# Power_Supplies.net
KiCad netlist of a schematic drawn in Altium Designer
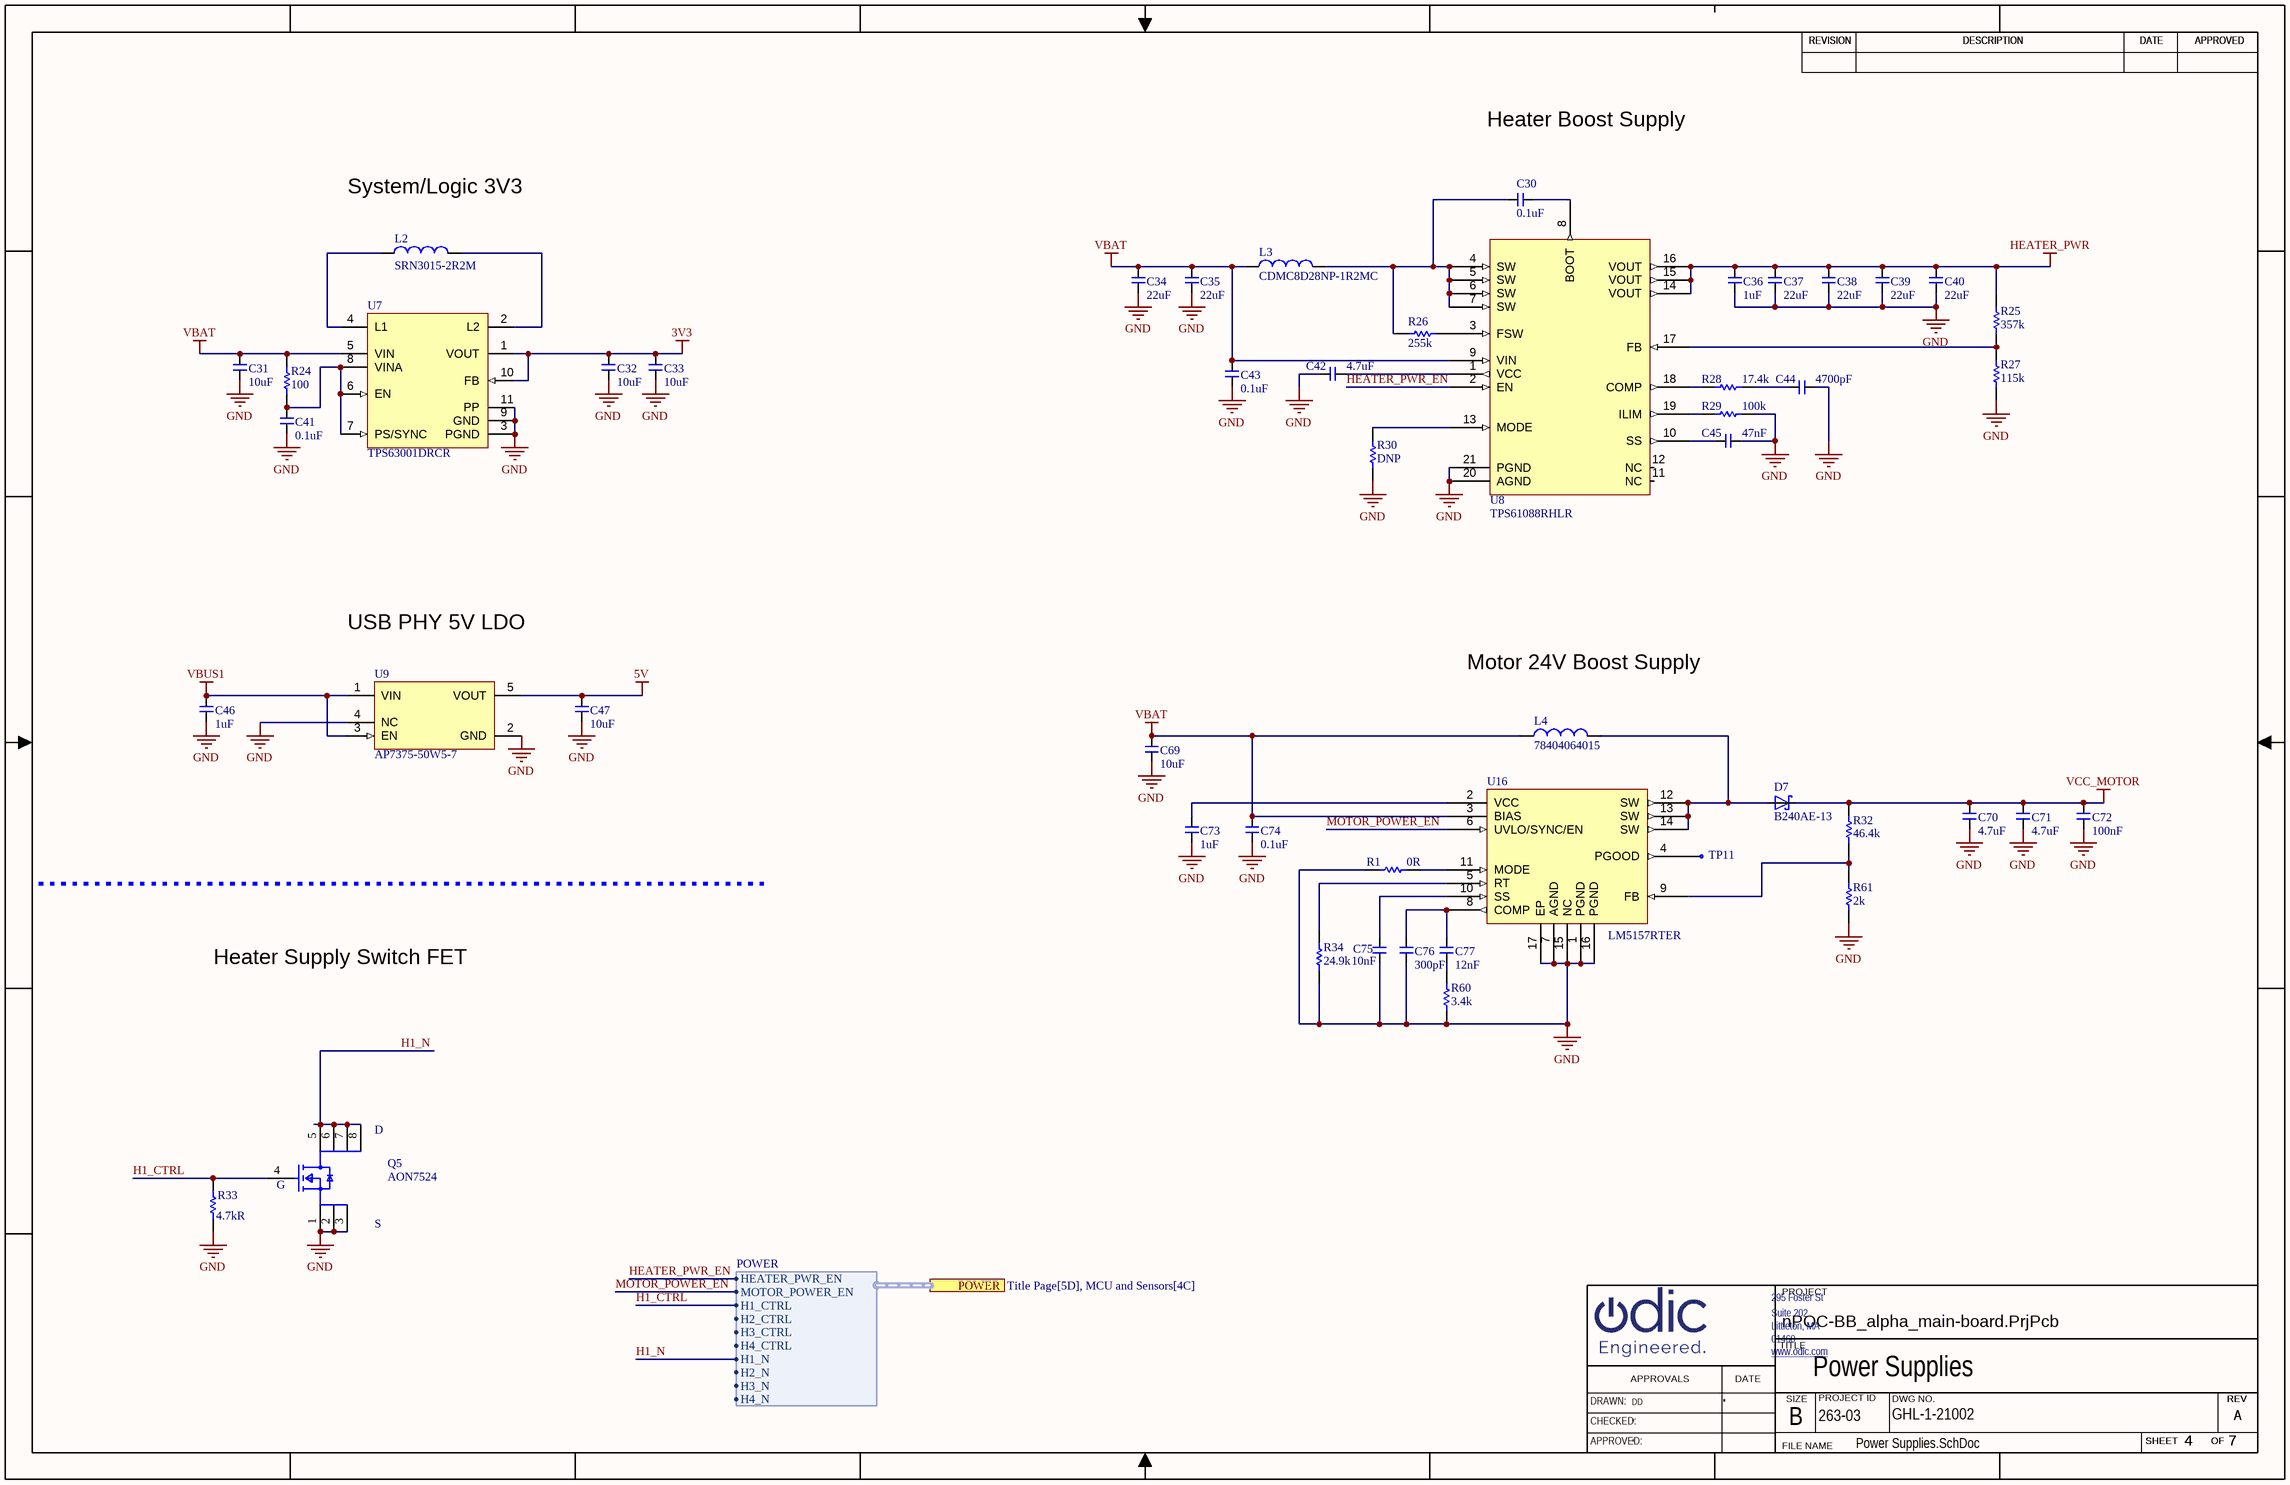
[diagram p0: Power Supplies.SchDoc]

(export (version "E")
  (design (tool "Eeschema 10.0.6"))
  (components
    (comp (ref "C30")
      (value "0.1uF")
      (footprint "C0402")
      (description "Ceramic capacitor SMD 0402 100nF 16V X7R 10%")
      (fields (field (name "VOLTAGE") "16V") (field (name "TOLERANCE") "10%"))
      (libsource (lib "Odic Inc") (part "cAP"))
    )
    (comp (ref "C31")
      (value "10uF")
      (footprint "C0603")
      (description "Cap Ceramic 10uF 35V X5R 20% Pad SMD 0603 85C T/R")
      (fields (field (name "TOLERANCE") "20%"))
      (libsource (lib "Odic Inc") (part "cAP"))
    )
    (comp (ref "C32")
      (value "10uF")
      (footprint "C0402")
      (description "Cap Ceramic 10uF 6.3V X5R 20% SMD 0402 85°C Paper T/R")
      (fields (field (name "TOLERANCE") "20%"))
      (libsource (lib "Odic Inc") (part "cAP"))
    )
    (comp (ref "C33")
      (value "10uF")
      (footprint "C0402")
      (description "Cap Ceramic 10uF 6.3V X5R 20% SMD 0402 85°C Paper T/R")
      (fields (field (name "TOLERANCE") "20%"))
      (libsource (lib "Odic Inc") (part "cAP"))
    )
    (comp (ref "C34")
      (value "22uF")
      (footprint "c0805")
      (description "Multilayer Ceramic Capacitor, 22 uF, 25 V, ± 20%, X5R, 0805 [2012 Metric]")
      (libsource (lib "Odic Inc") (part "cAP"))
    )
    (comp (ref "C35")
      (value "22uF")
      (footprint "c0805")
      (description "Multilayer Ceramic Capacitor, 22 uF, 25 V, ± 20%, X5R, 0805 [2012 Metric]")
      (libsource (lib "Odic Inc") (part "cAP"))
    )
    (comp (ref "C36")
      (value "1uF")
      (footprint "C0603")
      (description "Multilayer Ceramic Capacitors MLCC - SMD/SMT 1uF 50V 0603 RoHS")
      (fields (field (name "TOLERANCE") "10%"))
      (libsource (lib "Odic Inc") (part "cAP"))
    )
    (comp (ref "C37")
      (value "22uF")
      (footprint "c0805")
      (description "Multilayer Ceramic Capacitor, 22 uF, 25 V, ± 20%, X5R, 0805 [2012 Metric]")
      (libsource (lib "Odic Inc") (part "cAP"))
    )
    (comp (ref "C38")
      (value "22uF")
      (footprint "c0805")
      (description "Multilayer Ceramic Capacitor, 22 uF, 25 V, ± 20%, X5R, 0805 [2012 Metric]")
      (libsource (lib "Odic Inc") (part "cAP"))
    )
    (comp (ref "C39")
      (value "22uF")
      (footprint "c0805")
      (description "Multilayer Ceramic Capacitor, 22 uF, 25 V, ± 20%, X5R, 0805 [2012 Metric]")
      (libsource (lib "Odic Inc") (part "cAP"))
    )
    (comp (ref "C40")
      (value "22uF")
      (footprint "c0805")
      (description "Multilayer Ceramic Capacitor, 22 uF, 25 V, ± 20%, X5R, 0805 [2012 Metric]")
      (libsource (lib "Odic Inc") (part "cAP"))
    )
    (comp (ref "C41")
      (value "0.1uF")
      (footprint "C0402")
      (description "Cap Ceramic 0.1uF 25V X5R 10% Pad SMD 0402 Multi Layer Ceramic Capacitor (MLCC)")
      (fields (field (name "VOLTAGE") "25V") (field (name "TOLERANCE") "10%"))
      (libsource (lib "Odic Inc") (part "cAP"))
    )
    (comp (ref "C42")
      (value "4.7uF")
      (footprint "C0402")
      (description "Cap Ceramic 4.7uF 10V X5R 20% SMD 0402 85°C Paper T/R")
      (fields (field (name "TOLERANCE") "20%"))
      (libsource (lib "Odic Inc") (part "cAP"))
    )
    (comp (ref "C43")
      (value "0.1uF")
      (footprint "C0402")
      (description "Ceramic capacitor SMD 0402 100nF 16V X7R 10%")
      (fields (field (name "VOLTAGE") "16V") (field (name "TOLERANCE") "10%"))
      (libsource (lib "Odic Inc") (part "cAP"))
    )
    (comp (ref "C44")
      (value "4700pF")
      (footprint "C0402")
      (description "0402 4.7 nF 25 V ±10 % Tolerance X7R SMT Multilayer Ceramic Capacitor")
      (fields (field (name "TOLERANCE") "10%"))
      (libsource (lib "Odic Inc") (part "cAP"))
    )
    (comp (ref "C45")
      (value "47nF")
      (footprint "C0402")
      (description "CGA2B3X7R1H473K050BB")
      (fields (field (name "TOLERANCE") "10%"))
      (libsource (lib "Odic Inc") (part "cAP"))
    )
    (comp (ref "C46")
      (value "1uF")
      (footprint "C0603")
      (description "Multilayer Ceramic Capacitors MLCC - SMD/SMT 1uF 50V 0603 RoHS")
      (fields (field (name "TOLERANCE") "10%"))
      (libsource (lib "Odic Inc") (part "cAP"))
    )
    (comp (ref "C47")
      (value "10uF")
      (footprint "C0402")
      (description "Ceramic capacitor SMD; 0402; 10uF; 10V; X5R; 20%")
      (fields (field (name "TOLERANCE") "20%"))
      (libsource (lib "Odic Inc") (part "cAP"))
    )
    (comp (ref "C69")
      (value "10uF")
      (footprint "C0603")
      (description "Cap Ceramic 10uF 35V X5R 20% Pad SMD 0603 85C T/R")
      (fields (field (name "TOLERANCE") "20%"))
      (libsource (lib "Odic Inc") (part "cAP"))
    )
    (comp (ref "C70")
      (value "4.7uF")
      (footprint "c0805")
      (description "Multilayer Ceramic Capacitor, 4.7 uF, 35 V, ± 10%, X7S, 0805 [2012 Metric]")
      (fields (field (name "TOLERANCE") "10%"))
      (libsource (lib "Odic Inc") (part "cAP"))
    )
    (comp (ref "C71")
      (value "4.7uF")
      (footprint "c0805")
      (description "Multilayer Ceramic Capacitor, 4.7 uF, 35 V, ± 10%, X7S, 0805 [2012 Metric]")
      (fields (field (name "TOLERANCE") "10%"))
      (libsource (lib "Odic Inc") (part "cAP"))
    )
    (comp (ref "C72")
      (value "100nF")
      (footprint "C0603")
      (description "CAP CER 0.1UF 50V X7R 0603")
      (fields (field (name "TOLERANCE") "10%"))
      (libsource (lib "Odic Inc") (part "cAP"))
    )
    (comp (ref "C73")
      (value "1uF")
      (footprint "C0603")
      (description "CAP CER 1UF 16V X5R 0603")
      (fields (field (name "TOLERANCE") "10%") (field (name "VOLTAGE") "16V"))
      (libsource (lib "Odic Inc") (part "cAP"))
    )
    (comp (ref "C74")
      (value "0.1uF")
      (footprint "c0805")
      (description "Cap Cer 0.1UF 25V X7R 0805")
      (fields (field (name "TOLERANCE") "10%"))
      (libsource (lib "Odic Inc") (part "cAP"))
    )
    (comp (ref "C75")
      (value "10nF")
      (footprint "C0402")
      (description "Multilayer Ceramic Capacitor, 0.01 uF, 35 V, ± 10%, X7R, 0402 [1005 Metric]")
      (fields (field (name "TOLERANCE") "10%") (field (name "Comment") "C0402_10n_35V_10pct"))
      (libsource (lib "Odic Inc") (part "cAP"))
    )
    (comp (ref "C76")
      (value "300pF")
      (footprint "C0402")
      (description "Cap Ceramic 300pF 50V C0G 5% SMD 0402 125°C Paper T/R")
      (fields (field (name "TOLERANCE") "5%"))
      (libsource (lib "Odic Inc") (part "cAP"))
    )
    (comp (ref "C77")
      (value "12nF")
      (footprint "C0402")
      (description "0402 12 nF 16 V ±10% Tolerance X7R SMT Multilayer Ceramic Capacitor")
      (fields (field (name "VOLTAGE") "16V") (field (name "TOLERANCE") "10%"))
      (libsource (lib "Odic Inc") (part "cAP"))
    )
    (comp (ref "D7")
      (value "B240AE-13")
      (footprint "sma")
      (description "Diode Schottky 40V 2A 2-Pin DO-214AC T/R")
      (libsource (lib "Odic Inc") (part "B240AE-13"))
    )
    (comp (ref "L2")
      (value "SRN3015-2R2M")
      (footprint "IND_BOURNS_SRN3015")
      (description "Ind Power Semi-Shielded Wirewound 2.2uH 20% 1MHz Ferrite 1.8A 1212 T/R")
      (fields (field (name "TOLERANCE") "20%"))
      (libsource (lib "Odic Inc") (part "SRN3015-2R2M"))
    )
    (comp (ref "L3")
      (value "CDMC8D28NP-1R2MC")
      (footprint "ind2_9p5x8p5mm")
      (description "Inductor Power Shielded Wirewound 1.2uH 20% 1MHz 12.9A 0.007Ohm DCR T/R")
      (fields (field (name "TOLERANCE") "20%"))
      (libsource (lib "Odic Inc") (part "IND"))
    )
    (comp (ref "L4")
      (value "78404064015")
      (footprint "ind2_wurth_78404064015")
      (description "WE-LQSA SMT Semi-Shielded Power Inductor 1.5uH 6.1 A 13mOhm Max")
      (libsource (lib "Odic Inc") (part "IND"))
    )
    (comp (ref "Q5")
      (value "AON7524")
      (footprint "dfn8_3x3_p65mm_fet")
      (description "Trans Mosfet N-ch 30V 28A 8-PIN Dfn-a Ep")
      (libsource (lib "Odic Inc") (part "e0baf4780622716b99a4fe4ad34e686"))
    )
    (comp (ref "R1")
      (value "0R")
      (footprint "R0402")
      (description "RES 0 OHM JUMPER 1/16W 0402")
      (libsource (lib "Odic Inc") (part "RES"))
    )
    (comp (ref "R24")
      (value "100")
      (footprint "R0402")
      (description "Res General Purpose Thick Film 0402 100 Ohm 1% 1/16W ±200ppm/°C Molded SMD Paper T/R")
      (fields (field (name "TOLERANCE") "1%"))
      (libsource (lib "Odic Inc") (part "RES"))
    )
    (comp (ref "R25")
      (value "357k")
      (footprint "R0402")
      (description "Res Thick Film 0402 357K Ohm 1% 0.1W ±100ppm/°C Molded SMD Punched Carrier T/R")
      (fields (field (name "TOLERANCE") "1%"))
      (libsource (lib "Odic Inc") (part "RES"))
    )
    (comp (ref "R26")
      (value "255k")
      (footprint "R0402")
      (description "SMD Chip Resistor, 255 kOhm, ± 1%, 100 mW, 0402 [1005 Metric], Thick Film, Precision")
      (fields (field (name "TOLERANCE") "1%"))
      (libsource (lib "Odic Inc") (part "RES"))
    )
    (comp (ref "R27")
      (value "115k")
      (footprint "R0402")
      (description "SMD Chip Resistor, 115 kOhm, ± 1%, 100 mW, 0402 [1005 Metric], Thick Film, Precision")
      (fields (field (name "TOLERANCE") "1%"))
      (libsource (lib "Odic Inc") (part "RES"))
    )
    (comp (ref "R28")
      (value "17.4k")
      (footprint "R0402")
      (description "Res Thick Film 0402 17.4K Ohm 1% 1/10W ±100ppm/°C Molded SMD Punched Carrier T/R")
      (fields (field (name "TOLERANCE") "1%"))
      (libsource (lib "Odic Inc") (part "RES"))
    )
    (comp (ref "R29")
      (value "100k")
      (footprint "R0402")
      (description "Res General Purpose Thick Film 0402 100K Ohm 1% 1/16W ±100ppm/°C Molded SMD Paper T/R")
      (fields (field (name "TOLERANCE") "1%"))
      (libsource (lib "Odic Inc") (part "RES"))
    )
    (comp (ref "R30")
      (value "DNP")
      (footprint "R0402")
      (description "Unpopulated 0402 pads. No part number associated with this \"component\"")
      (libsource (lib "Odic Inc") (part "RES"))
    )
    (comp (ref "R32")
      (value "46.4k")
      (footprint "R0402")
      (description "Resistor, Metal Glaze/Thick Film, 0.1 W, 1 %, 100 Ppm, 46400 Ohm, Surface Mount, 0402")
      (fields (field (name "TOLERANCE") "1%"))
      (libsource (lib "Odic Inc") (part "RES"))
    )
    (comp (ref "R33")
      (value "R0402_4k7_1pct")
      (footprint "R0402")
      (description "RES 4.7K OHM 1% 1/16W 0402")
      (fields (field (name "TOLERANCE") "1%") (field (name "RESISTANCE") "4.7kR"))
      (libsource (lib "Odic Inc") (part "RES"))
    )
    (comp (ref "R34")
      (value "24.9k")
      (footprint "R0402")
      (description "Res Thick Film 0402 24.9K Ohm 1% 1/10W ±100ppm/¦C SMD Punched Carrier T/R")
      (fields (field (name "TOLERANCE") "1%"))
      (libsource (lib "Odic Inc") (part "RES"))
    )
    (comp (ref "R60")
      (value "3.4k")
      (footprint "R0402")
      (description "SMD Chip Resistor, 3.4 kOhm, ± 1%, 100 mW, 0402 [1005 Metric], Thick Film, Precision")
      (fields (field (name "TOLERANCE") "1%"))
      (libsource (lib "Odic Inc") (part "RES"))
    )
    (comp (ref "R61")
      (value "2k")
      (footprint "R0402")
      (description "Res General Purpose Thick Film 0402 2K Ohm 1% 1/16W ±100ppm/°C Molded SMD Paper T/R")
      (fields (field (name "TOLERANCE") "1%"))
      (libsource (lib "Odic Inc") (part "RES"))
    )
    (comp (ref "TP11")
      (value "TPC30")
      (footprint "tpc30")
      (description "Test Point Circle 30")
      (libsource (lib "Odic Inc") (part "TPC"))
    )
    (comp (ref "U7")
      (value "TPS63001DRCR")
      (footprint "dfn10_3x3_p5mm_1mm")
      (description "IC REG BUCK BST 3.3V 1.6A 10SON, FIXED 3.3V")
      (libsource (lib "Odic Inc") (part "TPS6300x"))
    )
    (comp (ref "U8")
      (value "TPS61088RHLR")
      (footprint "qfn20_3p5x4p5_p5mm")
      (description "IC REG BOOST ADJ 10A SYNC 20VQFN")
      (libsource (lib "Odic Inc") (part "TPS61088RHLR-Symbol-1"))
    )
    (comp (ref "U9")
      (value "AP7375-50W5-7")
      (footprint "SOT25")
      (description "Fixed 5V LDO Voltage Regulators LDO CMOS LowCurr SOT23 TR 3K")
      (libsource (lib "Odic Inc") (part "0611416dd6b6fc2280b1ddb1fddec67"))
    )
    (comp (ref "U16")
      (value "LM5157RTER")
      (footprint "qfn16_3x3_p5mm_thpad")
      (libsource (lib "Odic Inc") (part "LM5157RTER-Symbol-1"))
    )
  )
  (nets
    (net (code "2") (name "/H1_CTRL") (class "Default")
      (node (ref "Q5") (pin "4") (pinfunction "G_4") (pintype "passive"))
      (node (ref "R33") (pin "2") (pinfunction "2_2") (pintype "passive"))
    )
    (net (code "3") (name "/H1_N") (class "Default")
      (node (ref "Q5") (pin "5") (pinfunction "D_5") (pintype "passive"))
      (node (ref "Q5") (pin "6") (pinfunction "D_6") (pintype "passive"))
      (node (ref "Q5") (pin "7") (pinfunction "D_7") (pintype "passive"))
      (node (ref "Q5") (pin "8") (pinfunction "D_8") (pintype "passive"))
    )
    (net (code "4") (name "/HEATER_PWR_EN") (class "Default")
      (node (ref "U8") (pin "2") (pinfunction "EN_2") (pintype "input"))
    )
    (net (code "5") (name "/MOTOR_POWER_EN") (class "Default")
      (node (ref "U16") (pin "6") (pinfunction "UVLO/SYNC/EN_6") (pintype "input"))
    )
    (net (code "7") (name "3V3") (class "Default")
      (node (ref "C32") (pin "2") (pinfunction "2_2") (pintype "passive"))
      (node (ref "C33") (pin "2") (pinfunction "2_2") (pintype "passive"))
      (node (ref "U7") (pin "1") (pinfunction "VOUT_1") (pintype "power_in"))
      (node (ref "U7") (pin "10") (pinfunction "FB_10") (pintype "input"))
    )
    (net (code "8") (name "5V") (class "Default")
      (node (ref "C47") (pin "2") (pinfunction "2_2") (pintype "passive"))
      (node (ref "U9") (pin "5") (pinfunction "VOUT_5") (pintype "power_in"))
    )
    (net (code "9") (name "GND") (class "Default")
      (node (ref "C31") (pin "1") (pinfunction "1_1") (pintype "passive"))
      (node (ref "C32") (pin "1") (pinfunction "1_1") (pintype "passive"))
      (node (ref "C33") (pin "1") (pinfunction "1_1") (pintype "passive"))
      (node (ref "C34") (pin "1") (pinfunction "1_1") (pintype "passive"))
      (node (ref "C35") (pin "1") (pinfunction "1_1") (pintype "passive"))
      (node (ref "C36") (pin "1") (pinfunction "1_1") (pintype "passive"))
      (node (ref "C37") (pin "1") (pinfunction "1_1") (pintype "passive"))
      (node (ref "C38") (pin "1") (pinfunction "1_1") (pintype "passive"))
      (node (ref "C39") (pin "1") (pinfunction "1_1") (pintype "passive"))
      (node (ref "C40") (pin "1") (pinfunction "1_1") (pintype "passive"))
      (node (ref "C41") (pin "1") (pinfunction "1_1") (pintype "passive"))
      (node (ref "C42") (pin "1") (pinfunction "1_1") (pintype "passive"))
      (node (ref "C43") (pin "1") (pinfunction "1_1") (pintype "passive"))
      (node (ref "C44") (pin "2") (pinfunction "2_2") (pintype "passive"))
      (node (ref "C45") (pin "2") (pinfunction "2_2") (pintype "passive"))
      (node (ref "C46") (pin "1") (pinfunction "1_1") (pintype "passive"))
      (node (ref "C47") (pin "1") (pinfunction "1_1") (pintype "passive"))
      (node (ref "C69") (pin "1") (pinfunction "1_1") (pintype "passive"))
      (node (ref "C70") (pin "1") (pinfunction "1_1") (pintype "passive"))
      (node (ref "C71") (pin "1") (pinfunction "1_1") (pintype "passive"))
      (node (ref "C72") (pin "1") (pinfunction "1_1") (pintype "passive"))
      (node (ref "C73") (pin "1") (pinfunction "1_1") (pintype "passive"))
      (node (ref "C74") (pin "1") (pinfunction "1_1") (pintype "passive"))
      (node (ref "C75") (pin "1") (pinfunction "1_1") (pintype "passive"))
      (node (ref "C76") (pin "1") (pinfunction "1_1") (pintype "passive"))
      (node (ref "Q5") (pin "1") (pinfunction "S_1") (pintype "passive"))
      (node (ref "Q5") (pin "2") (pinfunction "S_2") (pintype "passive"))
      (node (ref "Q5") (pin "3") (pinfunction "S_3") (pintype "passive"))
      (node (ref "R1") (pin "1") (pinfunction "1_1") (pintype "passive"))
      (node (ref "R27") (pin "1") (pinfunction "1_1") (pintype "passive"))
      (node (ref "R29") (pin "2") (pinfunction "2_2") (pintype "passive"))
      (node (ref "R30") (pin "1") (pinfunction "1_1") (pintype "passive"))
      (node (ref "R33") (pin "1") (pinfunction "1_1") (pintype "passive"))
      (node (ref "R34") (pin "1") (pinfunction "1_1") (pintype "passive"))
      (node (ref "R60") (pin "1") (pinfunction "1_1") (pintype "passive"))
      (node (ref "R61") (pin "1") (pinfunction "1_1") (pintype "passive"))
      (node (ref "U16") (pin "1") (pinfunction "PGND_1") (pintype "passive"))
      (node (ref "U16") (pin "15") (pinfunction "NC_15") (pintype "passive"))
      (node (ref "U16") (pin "16") (pinfunction "PGND_16") (pintype "passive"))
      (node (ref "U16") (pin "17") (pinfunction "EP_17") (pintype "passive"))
      (node (ref "U16") (pin "7") (pinfunction "AGND_7") (pintype "passive"))
      (node (ref "U7") (pin "11") (pinfunction "PP_11") (pintype "power_in"))
      (node (ref "U7") (pin "3") (pinfunction "PGND_3") (pintype "power_in"))
      (node (ref "U7") (pin "9") (pinfunction "GND_9") (pintype "power_in"))
      (node (ref "U8") (pin "20") (pinfunction "AGND_20") (pintype "passive"))
      (node (ref "U8") (pin "21") (pinfunction "PGND_21") (pintype "passive"))
      (node (ref "U9") (pin "2") (pinfunction "GND_2") (pintype "power_in"))
      (node (ref "U9") (pin "4") (pinfunction "NC_4") (pintype "passive"))
    )
    (net (code "10") (name "HEATER_PWR") (class "Default")
      (node (ref "C36") (pin "2") (pinfunction "2_2") (pintype "passive"))
      (node (ref "C37") (pin "2") (pinfunction "2_2") (pintype "passive"))
      (node (ref "C38") (pin "2") (pinfunction "2_2") (pintype "passive"))
      (node (ref "C39") (pin "2") (pinfunction "2_2") (pintype "passive"))
      (node (ref "C40") (pin "2") (pinfunction "2_2") (pintype "passive"))
      (node (ref "R25") (pin "2") (pinfunction "2_2") (pintype "passive"))
      (node (ref "U8") (pin "14") (pinfunction "VOUT_14") (pintype "output"))
      (node (ref "U8") (pin "15") (pinfunction "VOUT_15") (pintype "output"))
      (node (ref "U8") (pin "16") (pinfunction "VOUT_16") (pintype "output"))
    )
    (net (code "11") (name "Net-(C30-Pad2)") (class "Default")
      (node (ref "C30") (pin "2") (pinfunction "2_2") (pintype "passive"))
      (node (ref "L3") (pin "2") (pinfunction "2_2") (pintype "passive"))
      (node (ref "R26") (pin "1") (pinfunction "1_1") (pintype "passive"))
      (node (ref "U8") (pin "4") (pinfunction "SW_4") (pintype "input"))
      (node (ref "U8") (pin "5") (pinfunction "SW_5") (pintype "input"))
      (node (ref "U8") (pin "6") (pinfunction "SW_6") (pintype "input"))
      (node (ref "U8") (pin "7") (pinfunction "SW_7") (pintype "input"))
    )
    (net (code "12") (name "Net-(C44-Pad1)") (class "Default")
      (node (ref "C44") (pin "1") (pinfunction "1_1") (pintype "passive"))
      (node (ref "R28") (pin "2") (pinfunction "2_2") (pintype "passive"))
    )
    (net (code "13") (name "Net-(C77-Pad1)") (class "Default")
      (node (ref "C77") (pin "1") (pinfunction "1_1") (pintype "passive"))
      (node (ref "R60") (pin "2") (pinfunction "2_2") (pintype "passive"))
    )
    (net (code "14") (name "Net-(D7-PadA)") (class "Default")
      (node (ref "D7") (pin "A") (pinfunction "A_A") (pintype "passive"))
      (node (ref "L4") (pin "2") (pinfunction "2_2") (pintype "passive"))
      (node (ref "U16") (pin "12") (pinfunction "SW_12") (pintype "output"))
      (node (ref "U16") (pin "13") (pinfunction "SW_13") (pintype "output"))
      (node (ref "U16") (pin "14") (pinfunction "SW_14") (pintype "output"))
    )
    (net (code "15") (name "Net-(U7-EN)") (class "Default")
      (node (ref "C41") (pin "2") (pinfunction "2_2") (pintype "passive"))
      (node (ref "R24") (pin "1") (pinfunction "1_1") (pintype "passive"))
      (node (ref "U7") (pin "6") (pinfunction "EN_6") (pintype "input"))
      (node (ref "U7") (pin "7") (pinfunction "PS/SYNC_7") (pintype "input"))
      (node (ref "U7") (pin "8") (pinfunction "VINA_8") (pintype "power_in"))
    )
    (net (code "16") (name "Net-(U7-L1)") (class "Default")
      (node (ref "L2") (pin "1") (pinfunction "1_1") (pintype "passive"))
      (node (ref "U7") (pin "4") (pinfunction "L1_4") (pintype "passive"))
    )
    (net (code "17") (name "Net-(U7-L2)") (class "Default")
      (node (ref "L2") (pin "2") (pinfunction "2_2") (pintype "passive"))
      (node (ref "U7") (pin "2") (pinfunction "L2_2") (pintype "passive"))
    )
    (net (code "18") (name "Net-(U8-BOOT)") (class "Default")
      (node (ref "C30") (pin "1") (pinfunction "1_1") (pintype "passive"))
      (node (ref "U8") (pin "8") (pinfunction "BOOT_8") (pintype "output"))
    )
    (net (code "19") (name "Net-(U8-COMP)") (class "Default")
      (node (ref "R28") (pin "1") (pinfunction "1_1") (pintype "passive"))
      (node (ref "U8") (pin "18") (pinfunction "COMP_18") (pintype "output"))
    )
    (net (code "20") (name "Net-(U8-FB)") (class "Default")
      (node (ref "R25") (pin "1") (pinfunction "1_1") (pintype "passive"))
      (node (ref "R27") (pin "2") (pinfunction "2_2") (pintype "passive"))
      (node (ref "U8") (pin "17") (pinfunction "FB_17") (pintype "input"))
    )
    (net (code "21") (name "Net-(U8-FSW)") (class "Default")
      (node (ref "R26") (pin "2") (pinfunction "2_2") (pintype "passive"))
      (node (ref "U8") (pin "3") (pinfunction "FSW_3") (pintype "input"))
    )
    (net (code "22") (name "Net-(U8-ILIM)") (class "Default")
      (node (ref "R29") (pin "1") (pinfunction "1_1") (pintype "passive"))
      (node (ref "U8") (pin "19") (pinfunction "ILIM_19") (pintype "output"))
    )
    (net (code "23") (name "Net-(U8-MODE)") (class "Default")
      (node (ref "R30") (pin "2") (pinfunction "2_2") (pintype "passive"))
      (node (ref "U8") (pin "13") (pinfunction "MODE_13") (pintype "input"))
    )
    (net (code "24") (name "Net-(U8-SS)") (class "Default")
      (node (ref "C45") (pin "1") (pinfunction "1_1") (pintype "passive"))
      (node (ref "U8") (pin "10") (pinfunction "SS_10") (pintype "output"))
    )
    (net (code "25") (name "Net-(U8-VCC)") (class "Default")
      (node (ref "C42") (pin "2") (pinfunction "2_2") (pintype "passive"))
      (node (ref "U8") (pin "1") (pinfunction "VCC_1") (pintype "output"))
    )
    (net (code "26") (name "Net-(U16-COMP)") (class "Default")
      (node (ref "C76") (pin "2") (pinfunction "2_2") (pintype "passive"))
      (node (ref "C77") (pin "2") (pinfunction "2_2") (pintype "passive"))
      (node (ref "U16") (pin "8") (pinfunction "COMP_8") (pintype "output"))
    )
    (net (code "27") (name "Net-(U16-FB)") (class "Default")
      (node (ref "R32") (pin "1") (pinfunction "1_1") (pintype "passive"))
      (node (ref "R61") (pin "2") (pinfunction "2_2") (pintype "passive"))
      (node (ref "U16") (pin "9") (pinfunction "FB_9") (pintype "input"))
    )
    (net (code "28") (name "Net-(U16-MODE)") (class "Default")
      (node (ref "R1") (pin "2") (pinfunction "2_2") (pintype "passive"))
      (node (ref "U16") (pin "11") (pinfunction "MODE_11") (pintype "input"))
    )
    (net (code "29") (name "Net-(U16-PGOOD)") (class "Default")
      (node (ref "TP11") (pin "1") (pinfunction "1_1") (pintype "passive"))
      (node (ref "U16") (pin "4") (pinfunction "PGOOD_4") (pintype "output"))
    )
    (net (code "30") (name "Net-(U16-RT)") (class "Default")
      (node (ref "R34") (pin "2") (pinfunction "2_2") (pintype "passive"))
      (node (ref "U16") (pin "5") (pinfunction "RT_5") (pintype "input"))
    )
    (net (code "31") (name "Net-(U16-SS)") (class "Default")
      (node (ref "C75") (pin "2") (pinfunction "2_2") (pintype "passive"))
      (node (ref "U16") (pin "10") (pinfunction "SS_10") (pintype "input"))
    )
    (net (code "32") (name "Net-(U16-VCC)") (class "Default")
      (node (ref "C73") (pin "2") (pinfunction "2_2") (pintype "passive"))
      (node (ref "U16") (pin "2") (pinfunction "VCC_2") (pintype "power_in"))
    )
    (net (code "33") (name "VBAT") (class "Default")
      (node (ref "C31") (pin "2") (pinfunction "2_2") (pintype "passive"))
      (node (ref "C34") (pin "2") (pinfunction "2_2") (pintype "passive"))
      (node (ref "C35") (pin "2") (pinfunction "2_2") (pintype "passive"))
      (node (ref "C43") (pin "2") (pinfunction "2_2") (pintype "passive"))
      (node (ref "C69") (pin "2") (pinfunction "2_2") (pintype "passive"))
      (node (ref "C74") (pin "2") (pinfunction "2_2") (pintype "passive"))
      (node (ref "L3") (pin "1") (pinfunction "1_1") (pintype "passive"))
      (node (ref "L4") (pin "1") (pinfunction "1_1") (pintype "passive"))
      (node (ref "R24") (pin "2") (pinfunction "2_2") (pintype "passive"))
      (node (ref "U16") (pin "3") (pinfunction "BIAS_3") (pintype "power_in"))
      (node (ref "U7") (pin "5") (pinfunction "VIN_5") (pintype "power_in"))
      (node (ref "U8") (pin "9") (pinfunction "VIN_9") (pintype "input"))
    )
    (net (code "34") (name "VBUS1") (class "Default")
      (node (ref "C46") (pin "2") (pinfunction "2_2") (pintype "passive"))
      (node (ref "U9") (pin "1") (pinfunction "VIN_1") (pintype "power_in"))
      (node (ref "U9") (pin "3") (pinfunction "EN_3") (pintype "input"))
    )
    (net (code "35") (name "VCC_MOTOR") (class "Default")
      (node (ref "C70") (pin "2") (pinfunction "2_2") (pintype "passive"))
      (node (ref "C71") (pin "2") (pinfunction "2_2") (pintype "passive"))
      (node (ref "C72") (pin "2") (pinfunction "2_2") (pintype "passive"))
      (node (ref "D7") (pin "K") (pinfunction "K_K") (pintype "passive"))
      (node (ref "R32") (pin "2") (pinfunction "2_2") (pintype "passive"))
    )
    (net (code "36") (name "unconnected-(U8-NC-Pad11)") (class "Default")
      (node (ref "U8") (pin "11") (pinfunction "NC_11") (pintype "passive"))
    )
    (net (code "37") (name "unconnected-(U8-NC-Pad12)") (class "Default")
      (node (ref "U8") (pin "12") (pinfunction "NC_12") (pintype "passive"))
    )
  )
)
